# well-siting-meter.net
KiCad netlist of a schematic drawn in EAGLE
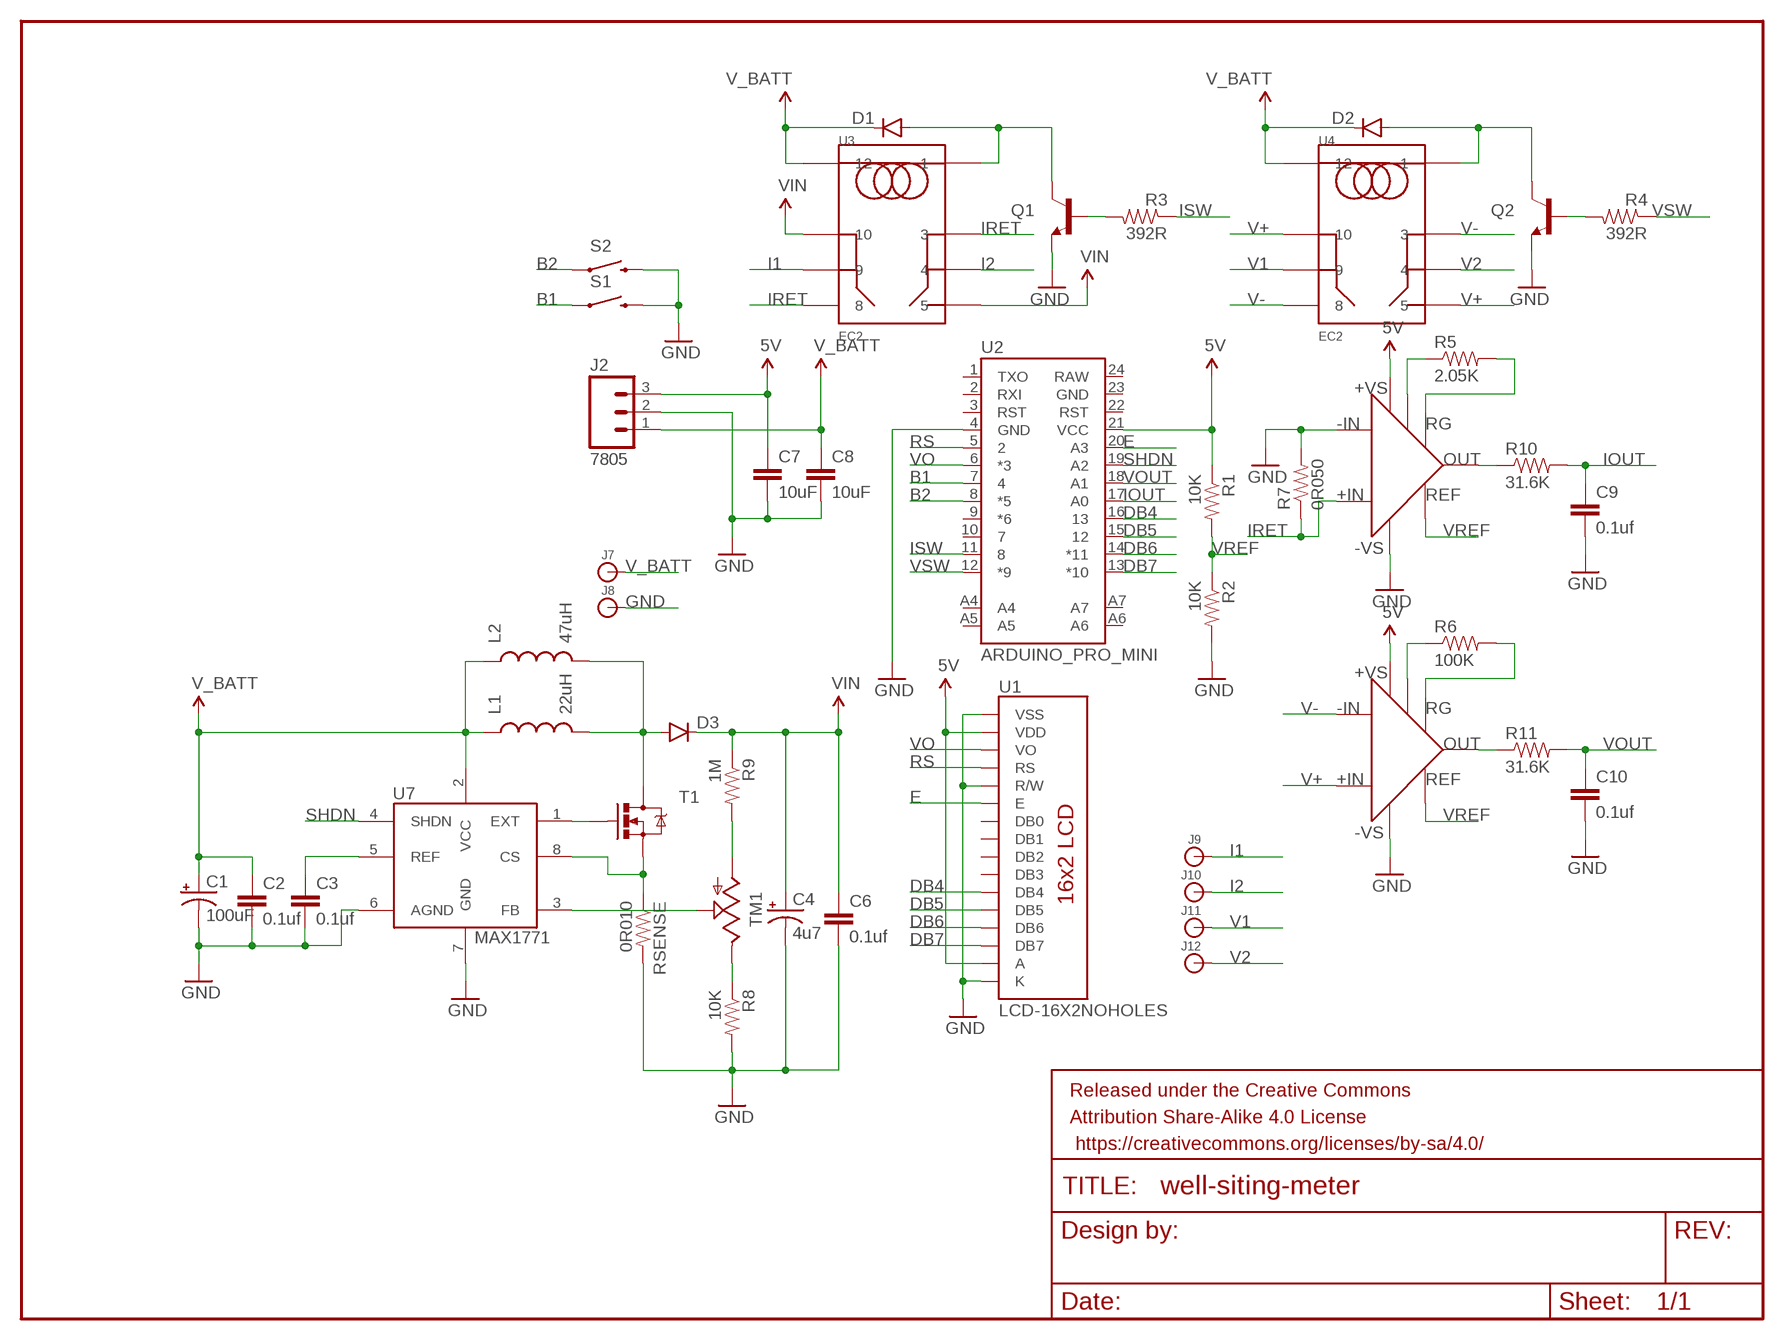
[diagram p0: schematic, sheet 1]

(export (version "E")
  (design (tool "Eeschema 10.0.6"))
  (components
    (comp (ref "C1")
      (value "100uF")
      (footprint "eagle-import:CPOL-RADIAL-1000UF-25V")
      (libsource (lib "eagle-import") (part "CAP_POLPTH4"))
    )
    (comp (ref "C2")
      (value "0.1uf")
      (footprint "eagle-import:CAP-PTH-5MM")
      (libsource (lib "eagle-import") (part "CAPPTH1"))
    )
    (comp (ref "C3")
      (value "0.1uf")
      (footprint "eagle-import:CAP-PTH-5MM")
      (libsource (lib "eagle-import") (part "CAPPTH1"))
    )
    (comp (ref "C4")
      (value "4u7")
      (footprint "eagle-import:CPOL-RADIAL-1000UF-25V")
      (libsource (lib "eagle-import") (part "CAP_POLPTH4"))
    )
    (comp (ref "C6")
      (value "0.1uf")
      (footprint "eagle-import:CAP-PTH-5MM")
      (libsource (lib "eagle-import") (part "CAPPTH1"))
    )
    (comp (ref "C7")
      (value "10uF")
      (footprint "eagle-import:CAP-PTH-5MM")
      (libsource (lib "eagle-import") (part "CAPPTH1"))
    )
    (comp (ref "C8")
      (value "10uF")
      (footprint "eagle-import:CAP-PTH-5MM")
      (libsource (lib "eagle-import") (part "CAPPTH1"))
    )
    (comp (ref "C9")
      (value "0.1uf")
      (footprint "eagle-import:CAP-PTH-5MM")
      (libsource (lib "eagle-import") (part "CAPPTH1"))
    )
    (comp (ref "C10")
      (value "0.1uf")
      (footprint "eagle-import:CAP-PTH-5MM")
      (libsource (lib "eagle-import") (part "CAPPTH1"))
    )
    (comp (ref "D1")
      (value "DIODEPTH")
      (footprint "eagle-import:DIODE-1N4001")
      (libsource (lib "eagle-import") (part "DIODEPTH"))
    )
    (comp (ref "D2")
      (value "DIODEPTH")
      (footprint "eagle-import:DIODE-1N4001")
      (libsource (lib "eagle-import") (part "DIODEPTH"))
    )
    (comp (ref "D3")
      (value "DIODEPTH")
      (footprint "eagle-import:DIODE-1N4001")
      (libsource (lib "eagle-import") (part "DIODEPTH"))
    )
    (comp (ref "FRAME1")
      (value "FRAME-LETTER")
      (footprint "eagle-import:CREATIVE_COMMONS")
      (libsource (lib "eagle-import") (part "FRAME-LETTER"))
    )
    (comp (ref "J2")
      (value "7805")
      (footprint "eagle-import:1X03")
      (libsource (lib "eagle-import") (part "M03PTH"))
    )
    (comp (ref "J7")
      (value "BANANA_CONN")
      (footprint "eagle-import:BANANA_CONN")
      (libsource (lib "eagle-import") (part "BANANA_CONN"))
    )
    (comp (ref "J8")
      (value "BANANA_CONN")
      (footprint "eagle-import:BANANA_CONN")
      (libsource (lib "eagle-import") (part "BANANA_CONN"))
    )
    (comp (ref "J9")
      (value "BANANA_CONN")
      (footprint "eagle-import:BANANA_CONN")
      (libsource (lib "eagle-import") (part "BANANA_CONN"))
    )
    (comp (ref "J10")
      (value "BANANA_CONN")
      (footprint "eagle-import:BANANA_CONN")
      (libsource (lib "eagle-import") (part "BANANA_CONN"))
    )
    (comp (ref "J11")
      (value "BANANA_CONN")
      (footprint "eagle-import:BANANA_CONN")
      (libsource (lib "eagle-import") (part "BANANA_CONN"))
    )
    (comp (ref "J12")
      (value "BANANA_CONN")
      (footprint "eagle-import:BANANA_CONN")
      (libsource (lib "eagle-import") (part "BANANA_CONN"))
    )
    (comp (ref "L1")
      (value "22uH")
      (footprint "eagle-import:1415")
      (libsource (lib "eagle-import") (part "WE-FAMI"))
    )
    (comp (ref "L2")
      (value "47uH")
      (footprint "eagle-import:MURATA1400")
      (libsource (lib "eagle-import") (part "MURATA1400"))
    )
    (comp (ref "Q1")
      (value "TRANSISTOR_NPNTO92")
      (footprint "eagle-import:TO-92")
      (libsource (lib "eagle-import") (part "TRANSISTOR_NPNTO92"))
    )
    (comp (ref "Q2")
      (value "TRANSISTOR_NPNTO92")
      (footprint "eagle-import:TO-92")
      (libsource (lib "eagle-import") (part "TRANSISTOR_NPNTO92"))
    )
    (comp (ref "R1")
      (value "10K")
      (footprint "eagle-import:AXIAL-0.4")
      (libsource (lib "eagle-import") (part "RESISTORPTH-1/4W"))
    )
    (comp (ref "R2")
      (value "10K")
      (footprint "eagle-import:AXIAL-0.4")
      (libsource (lib "eagle-import") (part "RESISTORPTH-1/4W"))
    )
    (comp (ref "R3")
      (value "392R")
      (footprint "eagle-import:AXIAL-0.4")
      (libsource (lib "eagle-import") (part "RESISTORPTH-1/4W"))
    )
    (comp (ref "R4")
      (value "392R")
      (footprint "eagle-import:AXIAL-0.4")
      (libsource (lib "eagle-import") (part "RESISTORPTH-1/4W"))
    )
    (comp (ref "R5")
      (value "2.05K")
      (footprint "eagle-import:AXIAL-0.4")
      (libsource (lib "eagle-import") (part "RESISTORPTH-1/4W"))
    )
    (comp (ref "R6")
      (value "100K")
      (footprint "eagle-import:AXIAL-0.4")
      (libsource (lib "eagle-import") (part "RESISTORPTH-1/4W"))
    )
    (comp (ref "R7")
      (value "0R050")
      (footprint "eagle-import:AXIAL-0.6")
      (libsource (lib "eagle-import") (part "RESISTORPTH-1W"))
    )
    (comp (ref "R8")
      (value "10K")
      (footprint "eagle-import:AXIAL-0.4")
      (libsource (lib "eagle-import") (part "RESISTORPTH-1/4W"))
    )
    (comp (ref "R9")
      (value "1M")
      (footprint "eagle-import:AXIAL-0.4")
      (libsource (lib "eagle-import") (part "RESISTORPTH-1/4W"))
    )
    (comp (ref "R10")
      (value "31.6K")
      (footprint "eagle-import:AXIAL-0.4")
      (libsource (lib "eagle-import") (part "RESISTORPTH-1/4W"))
    )
    (comp (ref "R11")
      (value "31.6K")
      (footprint "eagle-import:AXIAL-0.4")
      (libsource (lib "eagle-import") (part "RESISTORPTH-1/4W"))
    )
    (comp (ref "RSENSE")
      (value "0R010")
      (footprint "eagle-import:AXIAL-0.6")
      (libsource (lib "eagle-import") (part "RESISTORPTH-1W"))
    )
    (comp (ref "S1")
      (value "SWITCH-MOMENTARY-2PTH")
      (footprint "eagle-import:TACTILE-PTH")
      (libsource (lib "eagle-import") (part "SWITCH-MOMENTARY-2PTH"))
    )
    (comp (ref "S2")
      (value "SWITCH-MOMENTARY-2PTH")
      (footprint "eagle-import:TACTILE-PTH")
      (libsource (lib "eagle-import") (part "SWITCH-MOMENTARY-2PTH"))
    )
    (comp (ref "T1")
      (value "MOSFET-NCHANNELFQP30N06L")
      (footprint "eagle-import:TO220V")
      (libsource (lib "eagle-import") (part "MOSFET-NCHANNELFQP30N06L"))
    )
    (comp (ref "TM1")
      (value "TRIM3386")
      (footprint "eagle-import:TRIM-3386")
      (libsource (lib "eagle-import") (part "TRIM3386"))
    )
    (comp (ref "U1")
      (value "LCD-16X2NOHOLES")
      (footprint "eagle-import:LCD-16X2_NOHOLES")
      (libsource (lib "eagle-import") (part "LCD-16X2NOHOLES"))
    )
    (comp (ref "U2")
      (value "ARDUINO_PRO_MINI")
      (footprint "eagle-import:ARDUINO_PRO_MINI")
      (libsource (lib "eagle-import") (part "ARDUINO_PRO_MINI"))
    )
    (comp (ref "U3")
      (value "EC2")
      (footprint "eagle-import:EC2")
      (libsource (lib "eagle-import") (part "EC2"))
    )
    (comp (ref "U4")
      (value "EC2")
      (footprint "eagle-import:EC2")
      (libsource (lib "eagle-import") (part "EC2"))
    )
    (comp (ref "U5")
      (value "AD623")
      (footprint "eagle-import:DIP08")
      (libsource (lib "eagle-import") (part "AD623"))
    )
    (comp (ref "U6")
      (value "AD623")
      (footprint "eagle-import:DIP08")
      (libsource (lib "eagle-import") (part "AD623"))
    )
    (comp (ref "U7")
      (value "MAX1771")
      (footprint "eagle-import:DIP-08")
      (libsource (lib "eagle-import") (part "MAX1771"))
    )
  )
  (nets
    (net (code "1") (name "/B1") (class "Default")
      (node (ref "S1") (pin "1") (pinfunction "1_1") (pintype "passive"))
      (node (ref "U2") (pin "7") (pinfunction "4_7") (pintype "bidirectional"))
    )
    (net (code "2") (name "/B2") (class "Default")
      (node (ref "S2") (pin "1") (pinfunction "1_1") (pintype "passive"))
      (node (ref "U2") (pin "8") (pinfunction "*5_8") (pintype "bidirectional"))
    )
    (net (code "3") (name "/DB4") (class "Default")
      (node (ref "U1") (pin "11") (pinfunction "DB4_11") (pintype "bidirectional"))
      (node (ref "U2") (pin "16") (pinfunction "13_16") (pintype "bidirectional"))
    )
    (net (code "4") (name "/DB5") (class "Default")
      (node (ref "U1") (pin "12") (pinfunction "DB5_12") (pintype "bidirectional"))
      (node (ref "U2") (pin "15") (pinfunction "12_15") (pintype "bidirectional"))
    )
    (net (code "5") (name "/DB6") (class "Default")
      (node (ref "U1") (pin "13") (pinfunction "DB6_13") (pintype "bidirectional"))
      (node (ref "U2") (pin "14") (pinfunction "*11_14") (pintype "bidirectional"))
    )
    (net (code "6") (name "/DB7") (class "Default")
      (node (ref "U1") (pin "14") (pinfunction "DB7_14") (pintype "bidirectional"))
      (node (ref "U2") (pin "13") (pinfunction "*10_13") (pintype "bidirectional"))
    )
    (net (code "7") (name "/E") (class "Default")
      (node (ref "U1") (pin "6") (pinfunction "E_6") (pintype "input"))
      (node (ref "U2") (pin "20") (pinfunction "A3_20") (pintype "bidirectional"))
    )
    (net (code "8") (name "/I1") (class "Default")
      (node (ref "J9") (pin "P$1") (pinfunction "1_P$1") (pintype "passive"))
      (node (ref "U3") (pin "9") (pinfunction "9_9") (pintype "bidirectional"))
    )
    (net (code "9") (name "/I2") (class "Default")
      (node (ref "J10") (pin "P$1") (pinfunction "1_P$1") (pintype "passive"))
      (node (ref "U3") (pin "4") (pinfunction "4_4") (pintype "bidirectional"))
    )
    (net (code "10") (name "/IOUT") (class "Default")
      (node (ref "C9") (pin "1") (pinfunction "1_1") (pintype "passive"))
      (node (ref "R10") (pin "P$2") (pinfunction "2_P$2") (pintype "passive"))
      (node (ref "U2") (pin "17") (pinfunction "A0_17") (pintype "bidirectional"))
    )
    (net (code "11") (name "/IRET") (class "Default")
      (node (ref "R7") (pin "P$1") (pinfunction "1_P$1") (pintype "passive"))
      (node (ref "U3") (pin "3") (pinfunction "3_3") (pintype "bidirectional"))
      (node (ref "U3") (pin "8") (pinfunction "8_8") (pintype "bidirectional"))
      (node (ref "U5") (pin "3") (pinfunction "+IN_3") (pintype "bidirectional"))
    )
    (net (code "12") (name "/ISW") (class "Default")
      (node (ref "R3") (pin "P$1") (pinfunction "1_P$1") (pintype "passive"))
      (node (ref "U2") (pin "11") (pinfunction "8_11") (pintype "bidirectional"))
    )
    (net (code "13") (name "/RS") (class "Default")
      (node (ref "U1") (pin "4") (pinfunction "RS_4") (pintype "input"))
      (node (ref "U2") (pin "5") (pinfunction "2_5") (pintype "bidirectional"))
    )
    (net (code "14") (name "/SHDN") (class "Default")
      (node (ref "U2") (pin "19") (pinfunction "A2_19") (pintype "bidirectional"))
      (node (ref "U7") (pin "4") (pinfunction "SHDN_4") (pintype "input"))
    )
    (net (code "15") (name "/V+") (class "Default")
      (node (ref "U4") (pin "10") (pinfunction "10_10") (pintype "bidirectional"))
      (node (ref "U4") (pin "5") (pinfunction "5_5") (pintype "bidirectional"))
      (node (ref "U6") (pin "3") (pinfunction "+IN_3") (pintype "bidirectional"))
    )
    (net (code "16") (name "/V-") (class "Default")
      (node (ref "U4") (pin "3") (pinfunction "3_3") (pintype "bidirectional"))
      (node (ref "U4") (pin "8") (pinfunction "8_8") (pintype "bidirectional"))
      (node (ref "U6") (pin "2") (pinfunction "-IN_2") (pintype "bidirectional"))
    )
    (net (code "17") (name "/V1") (class "Default")
      (node (ref "J11") (pin "P$1") (pinfunction "1_P$1") (pintype "passive"))
      (node (ref "U4") (pin "9") (pinfunction "9_9") (pintype "bidirectional"))
    )
    (net (code "18") (name "/V2") (class "Default")
      (node (ref "J12") (pin "P$1") (pinfunction "1_P$1") (pintype "passive"))
      (node (ref "U4") (pin "4") (pinfunction "4_4") (pintype "bidirectional"))
    )
    (net (code "19") (name "/VO") (class "Default")
      (node (ref "U1") (pin "3") (pinfunction "VO_3") (pintype "bidirectional"))
      (node (ref "U2") (pin "6") (pinfunction "*3_6") (pintype "bidirectional"))
    )
    (net (code "20") (name "/VOUT") (class "Default")
      (node (ref "C10") (pin "1") (pinfunction "1_1") (pintype "passive"))
      (node (ref "R11") (pin "P$2") (pinfunction "2_P$2") (pintype "passive"))
      (node (ref "U2") (pin "18") (pinfunction "A1_18") (pintype "bidirectional"))
    )
    (net (code "21") (name "/VREF") (class "Default")
      (node (ref "R1") (pin "P$2") (pinfunction "2_P$2") (pintype "passive"))
      (node (ref "R2") (pin "P$1") (pinfunction "1_P$1") (pintype "passive"))
      (node (ref "U5") (pin "5") (pinfunction "REF_5") (pintype "bidirectional"))
      (node (ref "U6") (pin "5") (pinfunction "REF_5") (pintype "bidirectional"))
    )
    (net (code "22") (name "/VSW") (class "Default")
      (node (ref "R4") (pin "P$1") (pinfunction "1_P$1") (pintype "passive"))
      (node (ref "U2") (pin "12") (pinfunction "*9_12") (pintype "bidirectional"))
    )
    (net (code "23") (name "5V") (class "Default")
      (node (ref "C7") (pin "1") (pinfunction "1_1") (pintype "passive"))
      (node (ref "J2") (pin "3") (pinfunction "3_3") (pintype "passive"))
      (node (ref "R1") (pin "P$1") (pinfunction "1_P$1") (pintype "passive"))
      (node (ref "U1") (pin "15") (pinfunction "A_15") (pintype "power_in"))
      (node (ref "U1") (pin "2") (pinfunction "VDD_2") (pintype "power_in"))
      (node (ref "U2") (pin "21") (pinfunction "VCC_21") (pintype "bidirectional"))
      (node (ref "U5") (pin "7") (pinfunction "+VS_7") (pintype "bidirectional"))
      (node (ref "U6") (pin "7") (pinfunction "+VS_7") (pintype "bidirectional"))
    )
    (net (code "24") (name "GND") (class "Default")
      (node (ref "C1") (pin "2") (pinfunction "-_2") (pintype "passive"))
      (node (ref "C10") (pin "2") (pinfunction "2_2") (pintype "passive"))
      (node (ref "C2") (pin "2") (pinfunction "2_2") (pintype "passive"))
      (node (ref "C3") (pin "2") (pinfunction "2_2") (pintype "passive"))
      (node (ref "C4") (pin "2") (pinfunction "-_2") (pintype "passive"))
      (node (ref "C6") (pin "2") (pinfunction "2_2") (pintype "passive"))
      (node (ref "C7") (pin "2") (pinfunction "2_2") (pintype "passive"))
      (node (ref "C8") (pin "2") (pinfunction "2_2") (pintype "passive"))
      (node (ref "C9") (pin "2") (pinfunction "2_2") (pintype "passive"))
      (node (ref "J2") (pin "2") (pinfunction "2_2") (pintype "passive"))
      (node (ref "J8") (pin "P$1") (pinfunction "1_P$1") (pintype "passive"))
      (node (ref "Q1") (pin "1") (pinfunction "E_1") (pintype "passive"))
      (node (ref "Q2") (pin "1") (pinfunction "E_1") (pintype "passive"))
      (node (ref "R2") (pin "P$2") (pinfunction "2_P$2") (pintype "passive"))
      (node (ref "R7") (pin "P$2") (pinfunction "2_P$2") (pintype "passive"))
      (node (ref "R8") (pin "P$2") (pinfunction "2_P$2") (pintype "passive"))
      (node (ref "RSENSE") (pin "P$2") (pinfunction "2_P$2") (pintype "passive"))
      (node (ref "S1") (pin "3") (pinfunction "2_3") (pintype "passive"))
      (node (ref "S2") (pin "3") (pinfunction "2_3") (pintype "passive"))
      (node (ref "U1") (pin "1") (pinfunction "VSS_1") (pintype "power_in"))
      (node (ref "U1") (pin "16") (pinfunction "K_16") (pintype "power_in"))
      (node (ref "U1") (pin "5") (pinfunction "R/W_5") (pintype "input"))
      (node (ref "U2") (pin "4") (pinfunction "GND_4") (pintype "bidirectional"))
      (node (ref "U5") (pin "2") (pinfunction "-IN_2") (pintype "bidirectional"))
      (node (ref "U5") (pin "4") (pinfunction "-VS_4") (pintype "bidirectional"))
      (node (ref "U6") (pin "4") (pinfunction "-VS_4") (pintype "bidirectional"))
      (node (ref "U7") (pin "6") (pinfunction "AGND_6") (pintype "input"))
      (node (ref "U7") (pin "7") (pinfunction "GND_7") (pintype "input"))
    )
    (net (code "25") (name "Net-(L1-2)") (class "Default")
      (node (ref "D3") (pin "A") (pinfunction "A_A") (pintype "passive"))
      (node (ref "L1") (pin "P2") (pinfunction "2_P2") (pintype "passive"))
      (node (ref "L2") (pin "P$2") (pinfunction "2_P$2") (pintype "passive"))
      (node (ref "T1") (pin "2") (pinfunction "D_2") (pintype "passive"))
    )
    (net (code "26") (name "Net-(Q1-B)") (class "Default")
      (node (ref "Q1") (pin "2") (pinfunction "B_2") (pintype "passive"))
      (node (ref "R3") (pin "P$2") (pinfunction "2_P$2") (pintype "passive"))
    )
    (net (code "27") (name "Net-(Q1-C)") (class "Default")
      (node (ref "D1") (pin "A") (pinfunction "A_A") (pintype "passive"))
      (node (ref "Q1") (pin "3") (pinfunction "C_3") (pintype "passive"))
      (node (ref "U3") (pin "1") (pinfunction "1_1") (pintype "bidirectional"))
    )
    (net (code "28") (name "Net-(Q2-B)") (class "Default")
      (node (ref "Q2") (pin "2") (pinfunction "B_2") (pintype "passive"))
      (node (ref "R4") (pin "P$2") (pinfunction "2_P$2") (pintype "passive"))
    )
    (net (code "29") (name "Net-(Q2-C)") (class "Default")
      (node (ref "D2") (pin "A") (pinfunction "A_A") (pintype "passive"))
      (node (ref "Q2") (pin "3") (pinfunction "C_3") (pintype "passive"))
      (node (ref "U4") (pin "1") (pinfunction "1_1") (pintype "bidirectional"))
    )
    (net (code "30") (name "Net-(R5-1)") (class "Default")
      (node (ref "R5") (pin "P$1") (pinfunction "1_P$1") (pintype "passive"))
      (node (ref "U5") (pin "1") (pinfunction "-RG_1") (pintype "bidirectional"))
    )
    (net (code "31") (name "Net-(R5-2)") (class "Default")
      (node (ref "R5") (pin "P$2") (pinfunction "2_P$2") (pintype "passive"))
      (node (ref "U5") (pin "8") (pinfunction "+RG_8") (pintype "bidirectional"))
    )
    (net (code "32") (name "Net-(R6-1)") (class "Default")
      (node (ref "R6") (pin "P$1") (pinfunction "1_P$1") (pintype "passive"))
      (node (ref "U6") (pin "1") (pinfunction "-RG_1") (pintype "bidirectional"))
    )
    (net (code "33") (name "Net-(R6-2)") (class "Default")
      (node (ref "R6") (pin "P$2") (pinfunction "2_P$2") (pintype "passive"))
      (node (ref "U6") (pin "8") (pinfunction "+RG_8") (pintype "bidirectional"))
    )
    (net (code "34") (name "Net-(R8-1)") (class "Default")
      (node (ref "R8") (pin "P$1") (pinfunction "1_P$1") (pintype "passive"))
      (node (ref "TM1") (pin "1") (pinfunction "E_1") (pintype "passive"))
    )
    (net (code "35") (name "Net-(R9-2)") (class "Default")
      (node (ref "R9") (pin "P$2") (pinfunction "2_P$2") (pintype "passive"))
      (node (ref "TM1") (pin "3") (pinfunction "A_3") (pintype "passive"))
    )
    (net (code "36") (name "Net-(R10-1)") (class "Default")
      (node (ref "R10") (pin "P$1") (pinfunction "1_P$1") (pintype "passive"))
      (node (ref "U5") (pin "6") (pinfunction "OUT_6") (pintype "bidirectional"))
    )
    (net (code "37") (name "Net-(R11-1)") (class "Default")
      (node (ref "R11") (pin "P$1") (pinfunction "1_P$1") (pintype "passive"))
      (node (ref "U6") (pin "6") (pinfunction "OUT_6") (pintype "bidirectional"))
    )
    (net (code "38") (name "Net-(RSENSE-1)") (class "Default")
      (node (ref "RSENSE") (pin "P$1") (pinfunction "1_P$1") (pintype "passive"))
      (node (ref "T1") (pin "3") (pinfunction "S_3") (pintype "passive"))
      (node (ref "U7") (pin "8") (pinfunction "CS_8") (pintype "input"))
    )
    (net (code "39") (name "Net-(T1-G)") (class "Default")
      (node (ref "T1") (pin "1") (pinfunction "G_1") (pintype "passive"))
      (node (ref "U7") (pin "1") (pinfunction "EXT_1") (pintype "output"))
    )
    (net (code "40") (name "Net-(TM1-S)") (class "Default")
      (node (ref "TM1") (pin "2") (pinfunction "S_2") (pintype "passive"))
      (node (ref "U7") (pin "3") (pinfunction "FB_3") (pintype "input"))
    )
    (net (code "41") (name "Net-(U7-REF)") (class "Default")
      (node (ref "C3") (pin "1") (pinfunction "1_1") (pintype "passive"))
      (node (ref "U7") (pin "5") (pinfunction "REF_5") (pintype "input"))
    )
    (net (code "42") (name "VIN") (class "Default")
      (node (ref "C4") (pin "1") (pinfunction "+_1") (pintype "passive"))
      (node (ref "C6") (pin "1") (pinfunction "1_1") (pintype "passive"))
      (node (ref "D3") (pin "C") (pinfunction "C_C") (pintype "passive"))
      (node (ref "R9") (pin "P$1") (pinfunction "1_P$1") (pintype "passive"))
      (node (ref "U3") (pin "10") (pinfunction "10_10") (pintype "bidirectional"))
      (node (ref "U3") (pin "5") (pinfunction "5_5") (pintype "bidirectional"))
    )
    (net (code "43") (name "V_BATT") (class "Default")
      (node (ref "C1") (pin "1") (pinfunction "+_1") (pintype "passive"))
      (node (ref "C2") (pin "1") (pinfunction "1_1") (pintype "passive"))
      (node (ref "C8") (pin "1") (pinfunction "1_1") (pintype "passive"))
      (node (ref "D1") (pin "C") (pinfunction "C_C") (pintype "passive"))
      (node (ref "D2") (pin "C") (pinfunction "C_C") (pintype "passive"))
      (node (ref "J2") (pin "1") (pinfunction "1_1") (pintype "passive"))
      (node (ref "J7") (pin "P$1") (pinfunction "1_P$1") (pintype "passive"))
      (node (ref "L1") (pin "P1") (pinfunction "1_P1") (pintype "passive"))
      (node (ref "L2") (pin "P$1") (pinfunction "1_P$1") (pintype "passive"))
      (node (ref "U3") (pin "12") (pinfunction "12_12") (pintype "bidirectional"))
      (node (ref "U4") (pin "12") (pinfunction "12_12") (pintype "bidirectional"))
      (node (ref "U7") (pin "2") (pinfunction "VCC_2") (pintype "input"))
    )
    (net (code "44") (name "unconnected-(U1-DB0-Pad7)") (class "Default")
      (node (ref "U1") (pin "7") (pinfunction "DB0_7") (pintype "bidirectional"))
    )
    (net (code "45") (name "unconnected-(U1-DB1-Pad8)") (class "Default")
      (node (ref "U1") (pin "8") (pinfunction "DB1_8") (pintype "bidirectional"))
    )
    (net (code "46") (name "unconnected-(U1-DB2-Pad9)") (class "Default")
      (node (ref "U1") (pin "9") (pinfunction "DB2_9") (pintype "bidirectional"))
    )
    (net (code "47") (name "unconnected-(U1-DB3-Pad10)") (class "Default")
      (node (ref "U1") (pin "10") (pinfunction "DB3_10") (pintype "bidirectional"))
    )
    (net (code "48") (name "unconnected-(U2-*6-Pad9)") (class "Default")
      (node (ref "U2") (pin "9") (pinfunction "*6_9") (pintype "bidirectional"))
    )
    (net (code "49") (name "unconnected-(U2-7-Pad10)") (class "Default")
      (node (ref "U2") (pin "10") (pinfunction "7_10") (pintype "bidirectional"))
    )
    (net (code "50") (name "unconnected-(U2-GND-Pad23)") (class "Default")
      (node (ref "U2") (pin "23") (pinfunction "GND_23") (pintype "bidirectional"))
    )
    (net (code "51") (name "unconnected-(U2-PadA4)") (class "Default")
      (node (ref "U2") (pin "A4") (pinfunction "A4_A4") (pintype "bidirectional"))
    )
    (net (code "52") (name "unconnected-(U2-PadA5)") (class "Default")
      (node (ref "U2") (pin "A5") (pinfunction "A5_A5") (pintype "bidirectional"))
    )
    (net (code "53") (name "unconnected-(U2-PadA6)") (class "Default")
      (node (ref "U2") (pin "A6") (pinfunction "A6_A6") (pintype "bidirectional"))
    )
    (net (code "54") (name "unconnected-(U2-PadA7)") (class "Default")
      (node (ref "U2") (pin "A7") (pinfunction "A7_A7") (pintype "bidirectional"))
    )
    (net (code "55") (name "unconnected-(U2-RAW-Pad24)") (class "Default")
      (node (ref "U2") (pin "24") (pinfunction "RAW_24") (pintype "bidirectional"))
    )
    (net (code "56") (name "unconnected-(U2-RST-Pad3)") (class "Default")
      (node (ref "U2") (pin "3") (pinfunction "RST_3") (pintype "bidirectional"))
    )
    (net (code "57") (name "unconnected-(U2-RST-Pad22)") (class "Default")
      (node (ref "U2") (pin "22") (pinfunction "RST_22") (pintype "bidirectional"))
    )
    (net (code "58") (name "unconnected-(U2-RXI-Pad2)") (class "Default")
      (node (ref "U2") (pin "2") (pinfunction "RXI_2") (pintype "bidirectional"))
    )
    (net (code "59") (name "unconnected-(U2-TXO-Pad1)") (class "Default")
      (node (ref "U2") (pin "1") (pinfunction "TXO_1") (pintype "bidirectional"))
    )
  )
)
